# motor_PCB.net
KiCad netlist of a schematic drawn in EAGLE
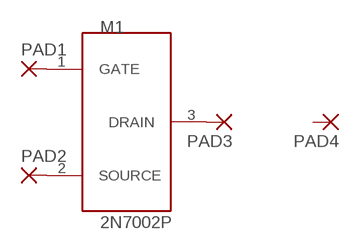
[diagram p0: schematic, sheet 1]

(export (version "E")
  (design (tool "Eeschema 10.0.6"))
  (components
    (comp (ref "M1")
      (value "2N7002P")
      (footprint "eagle-import:TO-236AB")
      (libsource (lib "eagle-import") (part "2N7002P"))
    )
    (comp (ref "PAD1")
      (value "SMD2")
      (footprint "eagle-import:SMD1,27-2,54")
      (libsource (lib "eagle-import") (part "SMD2"))
    )
    (comp (ref "PAD2")
      (value "SMD2")
      (footprint "eagle-import:SMD1,27-2,54")
      (libsource (lib "eagle-import") (part "SMD2"))
    )
    (comp (ref "PAD3")
      (value "SMD2")
      (footprint "eagle-import:SMD1,27-2,54")
      (libsource (lib "eagle-import") (part "SMD2"))
    )
    (comp (ref "PAD4")
      (value "SMD2")
      (footprint "eagle-import:SMD1,27-2,54")
      (libsource (lib "eagle-import") (part "SMD2"))
    )
  )
  (nets
    (net (code "1") (name "Net-(M1-DRAIN)") (class "Default")
      (node (ref "M1") (pin "3") (pinfunction "DRAIN_3") (pintype "bidirectional"))
      (node (ref "PAD3") (pin "1") (pinfunction "P_1") (pintype "passive"))
    )
    (net (code "2") (name "Net-(M1-GATE)") (class "Default")
      (node (ref "M1") (pin "1") (pinfunction "GATE_1") (pintype "bidirectional"))
      (node (ref "PAD1") (pin "1") (pinfunction "P_1") (pintype "passive"))
    )
    (net (code "3") (name "Net-(M1-SOURCE)") (class "Default")
      (node (ref "M1") (pin "2") (pinfunction "SOURCE_2") (pintype "bidirectional"))
      (node (ref "PAD2") (pin "1") (pinfunction "P_1") (pintype "passive"))
    )
    (net (code "4") (name "unconnected-(PAD4-P-Pad1)") (class "Default")
      (node (ref "PAD4") (pin "1") (pinfunction "P_1") (pintype "passive"))
    )
  )
)
